# PORTS_DRIVER.net
KiCad netlist of a schematic drawn in Altium Designer
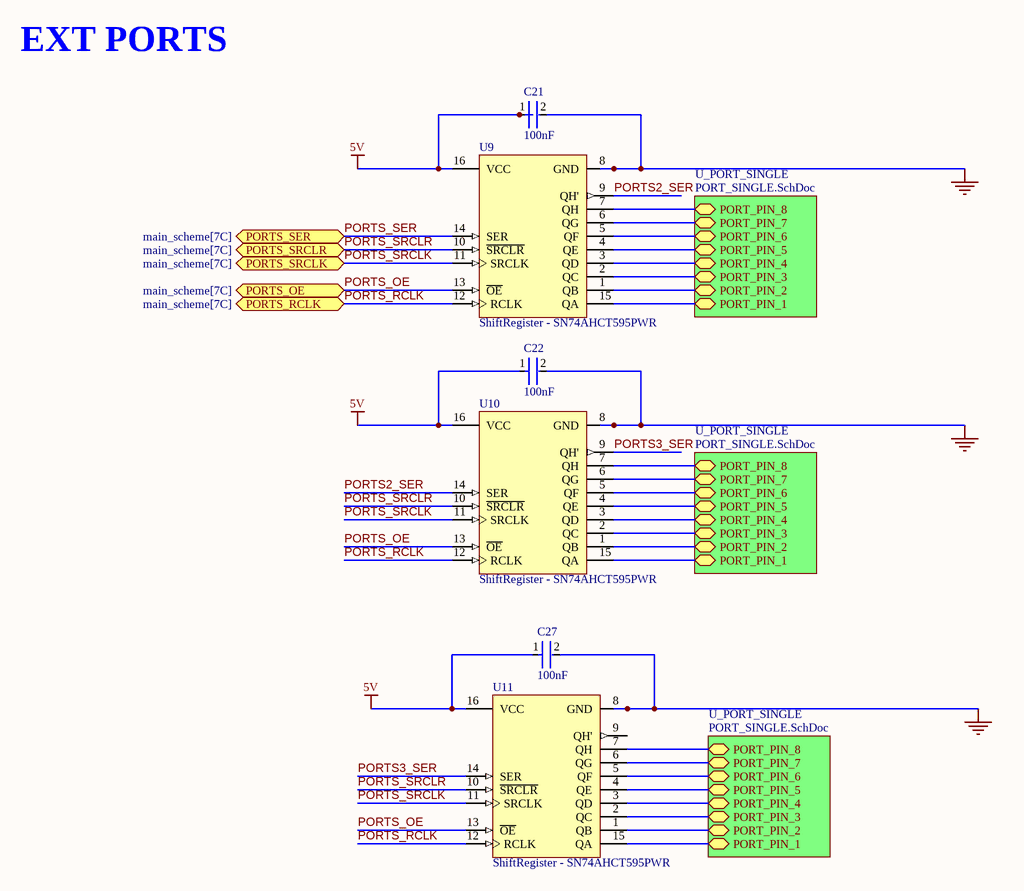
[diagram p0: PORTS_DRIVER.SchDoc]

(export (version "E")
  (design (tool "Eeschema 10.0.6"))
  (components
    (comp (ref "C21")
      (value "100nF")
      (footprint "0402 CAP")
      (description "Cap Ceramic 0402,0.1uF, 25V,10%")
      (fields (field (name "PARTNUMBER") "C0402C104K3RACTU"))
      (libsource (lib "Schlib1") (part "CAP 0402 - 100nF"))
    )
    (comp (ref "C22")
      (value "100nF")
      (footprint "0402 CAP")
      (description "Cap Ceramic 0402,0.1uF, 25V,10%")
      (fields (field (name "PARTNUMBER") "C0402C104K3RACTU"))
      (libsource (lib "Schlib1") (part "CAP 0402 - 100nF"))
    )
    (comp (ref "C27")
      (value "100nF")
      (footprint "0402 CAP")
      (description "Cap Ceramic 0402,0.1uF, 25V,10%")
      (fields (field (name "PARTNUMBER") "C0402C104K3RACTU"))
      (libsource (lib "Schlib1") (part "CAP 0402 - 100nF"))
    )
    (comp (ref "U9")
      (value "ShiftRegister - SN74AHCT595PWR")
      (footprint "SSOT16")
      (description "8-Bit Shift Registers With 3-State Output Registers, PW0016A, LARGE T&R")
      (fields (field (name "PARTNUMBER") "SN74AHCT595PWR"))
      (libsource (lib "Schlib1") (part "ShiftRegister - SN74AHCT595PWR"))
    )
    (comp (ref "U10")
      (value "ShiftRegister - SN74AHCT595PWR")
      (footprint "SSOT16")
      (description "8-Bit Shift Registers With 3-State Output Registers, PW0016A, LARGE T&R")
      (fields (field (name "PARTNUMBER") "SN74AHCT595PWR"))
      (libsource (lib "Schlib1") (part "ShiftRegister - SN74AHCT595PWR"))
    )
    (comp (ref "U11")
      (value "ShiftRegister - SN74AHCT595PWR")
      (footprint "SSOT16")
      (description "8-Bit Shift Registers With 3-State Output Registers, PW0016A, LARGE T&R")
      (fields (field (name "PARTNUMBER") "SN74AHCT595PWR"))
      (libsource (lib "Schlib1") (part "ShiftRegister - SN74AHCT595PWR"))
    )
  )
  (nets
    (net (code "1") (name "/PORTS2_SER") (class "Default")
      (node (ref "U10") (pin "14") (pinfunction "SER_14") (pintype "input"))
      (node (ref "U9") (pin "9") (pinfunction "QH'_9") (pintype "output"))
    )
    (net (code "2") (name "/PORTS3_SER") (class "Default")
      (node (ref "U10") (pin "9") (pinfunction "QH'_9") (pintype "output"))
      (node (ref "U11") (pin "14") (pinfunction "SER_14") (pintype "input"))
    )
    (net (code "3") (name "/PORTS_OE") (class "Default")
      (node (ref "U10") (pin "13") (pinfunction "~{OE}_13") (pintype "input"))
      (node (ref "U11") (pin "13") (pinfunction "~{OE}_13") (pintype "input"))
      (node (ref "U9") (pin "13") (pinfunction "~{OE}_13") (pintype "input"))
    )
    (net (code "4") (name "/PORTS_RCLK") (class "Default")
      (node (ref "U10") (pin "12") (pinfunction "RCLK_12") (pintype "input"))
      (node (ref "U11") (pin "12") (pinfunction "RCLK_12") (pintype "input"))
      (node (ref "U9") (pin "12") (pinfunction "RCLK_12") (pintype "input"))
    )
    (net (code "5") (name "/PORTS_SER") (class "Default")
      (node (ref "U9") (pin "14") (pinfunction "SER_14") (pintype "input"))
    )
    (net (code "6") (name "/PORTS_SRCLK") (class "Default")
      (node (ref "U10") (pin "11") (pinfunction "SRCLK_11") (pintype "input"))
      (node (ref "U11") (pin "11") (pinfunction "SRCLK_11") (pintype "input"))
      (node (ref "U9") (pin "11") (pinfunction "SRCLK_11") (pintype "input"))
    )
    (net (code "7") (name "/PORTS_SRCLR") (class "Default")
      (node (ref "U10") (pin "10") (pinfunction "~{SRCLR}_10") (pintype "input"))
      (node (ref "U11") (pin "10") (pinfunction "~{SRCLR}_10") (pintype "input"))
      (node (ref "U9") (pin "10") (pinfunction "~{SRCLR}_10") (pintype "input"))
    )
    (net (code "8") (name "/PORT_PIN_1") (class "Default")
      (node (ref "U10") (pin "15") (pinfunction "QA_15") (pintype "tri_state"))
    )
    (net (code "9") (name "/PORT_PIN_1_1") (class "Default")
      (node (ref "U9") (pin "15") (pinfunction "QA_15") (pintype "tri_state"))
    )
    (net (code "10") (name "/PORT_PIN_1_2") (class "Default")
      (node (ref "U11") (pin "15") (pinfunction "QA_15") (pintype "tri_state"))
    )
    (net (code "11") (name "/PORT_PIN_2") (class "Default")
      (node (ref "U10") (pin "1") (pinfunction "QB_1") (pintype "tri_state"))
    )
    (net (code "12") (name "/PORT_PIN_2_1") (class "Default")
      (node (ref "U9") (pin "1") (pinfunction "QB_1") (pintype "tri_state"))
    )
    (net (code "13") (name "/PORT_PIN_2_2") (class "Default")
      (node (ref "U11") (pin "1") (pinfunction "QB_1") (pintype "tri_state"))
    )
    (net (code "14") (name "/PORT_PIN_3") (class "Default")
      (node (ref "U10") (pin "2") (pinfunction "QC_2") (pintype "tri_state"))
    )
    (net (code "15") (name "/PORT_PIN_3_1") (class "Default")
      (node (ref "U9") (pin "2") (pinfunction "QC_2") (pintype "tri_state"))
    )
    (net (code "16") (name "/PORT_PIN_3_2") (class "Default")
      (node (ref "U11") (pin "2") (pinfunction "QC_2") (pintype "tri_state"))
    )
    (net (code "17") (name "/PORT_PIN_4") (class "Default")
      (node (ref "U10") (pin "3") (pinfunction "QD_3") (pintype "tri_state"))
    )
    (net (code "18") (name "/PORT_PIN_4_1") (class "Default")
      (node (ref "U9") (pin "3") (pinfunction "QD_3") (pintype "tri_state"))
    )
    (net (code "19") (name "/PORT_PIN_4_2") (class "Default")
      (node (ref "U11") (pin "3") (pinfunction "QD_3") (pintype "tri_state"))
    )
    (net (code "20") (name "/PORT_PIN_5") (class "Default")
      (node (ref "U10") (pin "4") (pinfunction "QE_4") (pintype "tri_state"))
    )
    (net (code "21") (name "/PORT_PIN_5_1") (class "Default")
      (node (ref "U9") (pin "4") (pinfunction "QE_4") (pintype "tri_state"))
    )
    (net (code "22") (name "/PORT_PIN_5_2") (class "Default")
      (node (ref "U11") (pin "4") (pinfunction "QE_4") (pintype "tri_state"))
    )
    (net (code "23") (name "/PORT_PIN_6") (class "Default")
      (node (ref "U10") (pin "5") (pinfunction "QF_5") (pintype "tri_state"))
    )
    (net (code "24") (name "/PORT_PIN_6_1") (class "Default")
      (node (ref "U9") (pin "5") (pinfunction "QF_5") (pintype "tri_state"))
    )
    (net (code "25") (name "/PORT_PIN_6_2") (class "Default")
      (node (ref "U11") (pin "5") (pinfunction "QF_5") (pintype "tri_state"))
    )
    (net (code "26") (name "/PORT_PIN_7") (class "Default")
      (node (ref "U10") (pin "6") (pinfunction "QG_6") (pintype "tri_state"))
    )
    (net (code "27") (name "/PORT_PIN_7_1") (class "Default")
      (node (ref "U9") (pin "6") (pinfunction "QG_6") (pintype "tri_state"))
    )
    (net (code "28") (name "/PORT_PIN_7_2") (class "Default")
      (node (ref "U11") (pin "6") (pinfunction "QG_6") (pintype "tri_state"))
    )
    (net (code "29") (name "/PORT_PIN_8") (class "Default")
      (node (ref "U10") (pin "7") (pinfunction "QH_7") (pintype "tri_state"))
    )
    (net (code "30") (name "/PORT_PIN_8_1") (class "Default")
      (node (ref "U9") (pin "7") (pinfunction "QH_7") (pintype "tri_state"))
    )
    (net (code "31") (name "/PORT_PIN_8_2") (class "Default")
      (node (ref "U11") (pin "7") (pinfunction "QH_7") (pintype "tri_state"))
    )
    (net (code "32") (name "5V") (class "Default")
      (node (ref "C21") (pin "1") (pinfunction "1_1") (pintype "passive"))
      (node (ref "C22") (pin "1") (pinfunction "1_1") (pintype "passive"))
      (node (ref "C27") (pin "1") (pinfunction "1_1") (pintype "passive"))
      (node (ref "U10") (pin "16") (pinfunction "VCC_16") (pintype "power_in"))
      (node (ref "U11") (pin "16") (pinfunction "VCC_16") (pintype "power_in"))
      (node (ref "U9") (pin "16") (pinfunction "VCC_16") (pintype "power_in"))
    )
    (net (code "33") (name "GND") (class "Default")
      (node (ref "C21") (pin "2") (pinfunction "2_2") (pintype "passive"))
      (node (ref "C22") (pin "2") (pinfunction "2_2") (pintype "passive"))
      (node (ref "C27") (pin "2") (pinfunction "2_2") (pintype "passive"))
      (node (ref "U10") (pin "8") (pinfunction "GND_8") (pintype "power_in"))
      (node (ref "U11") (pin "8") (pinfunction "GND_8") (pintype "power_in"))
      (node (ref "U9") (pin "8") (pinfunction "GND_8") (pintype "power_in"))
    )
    (net (code "34") (name "unconnected-(U11-QH'-Pad9)") (class "Default")
      (node (ref "U11") (pin "9") (pinfunction "QH'_9") (pintype "output"))
    )
  )
)
